# motor_controller_logic.net
KiCad netlist of a schematic drawn in EAGLE
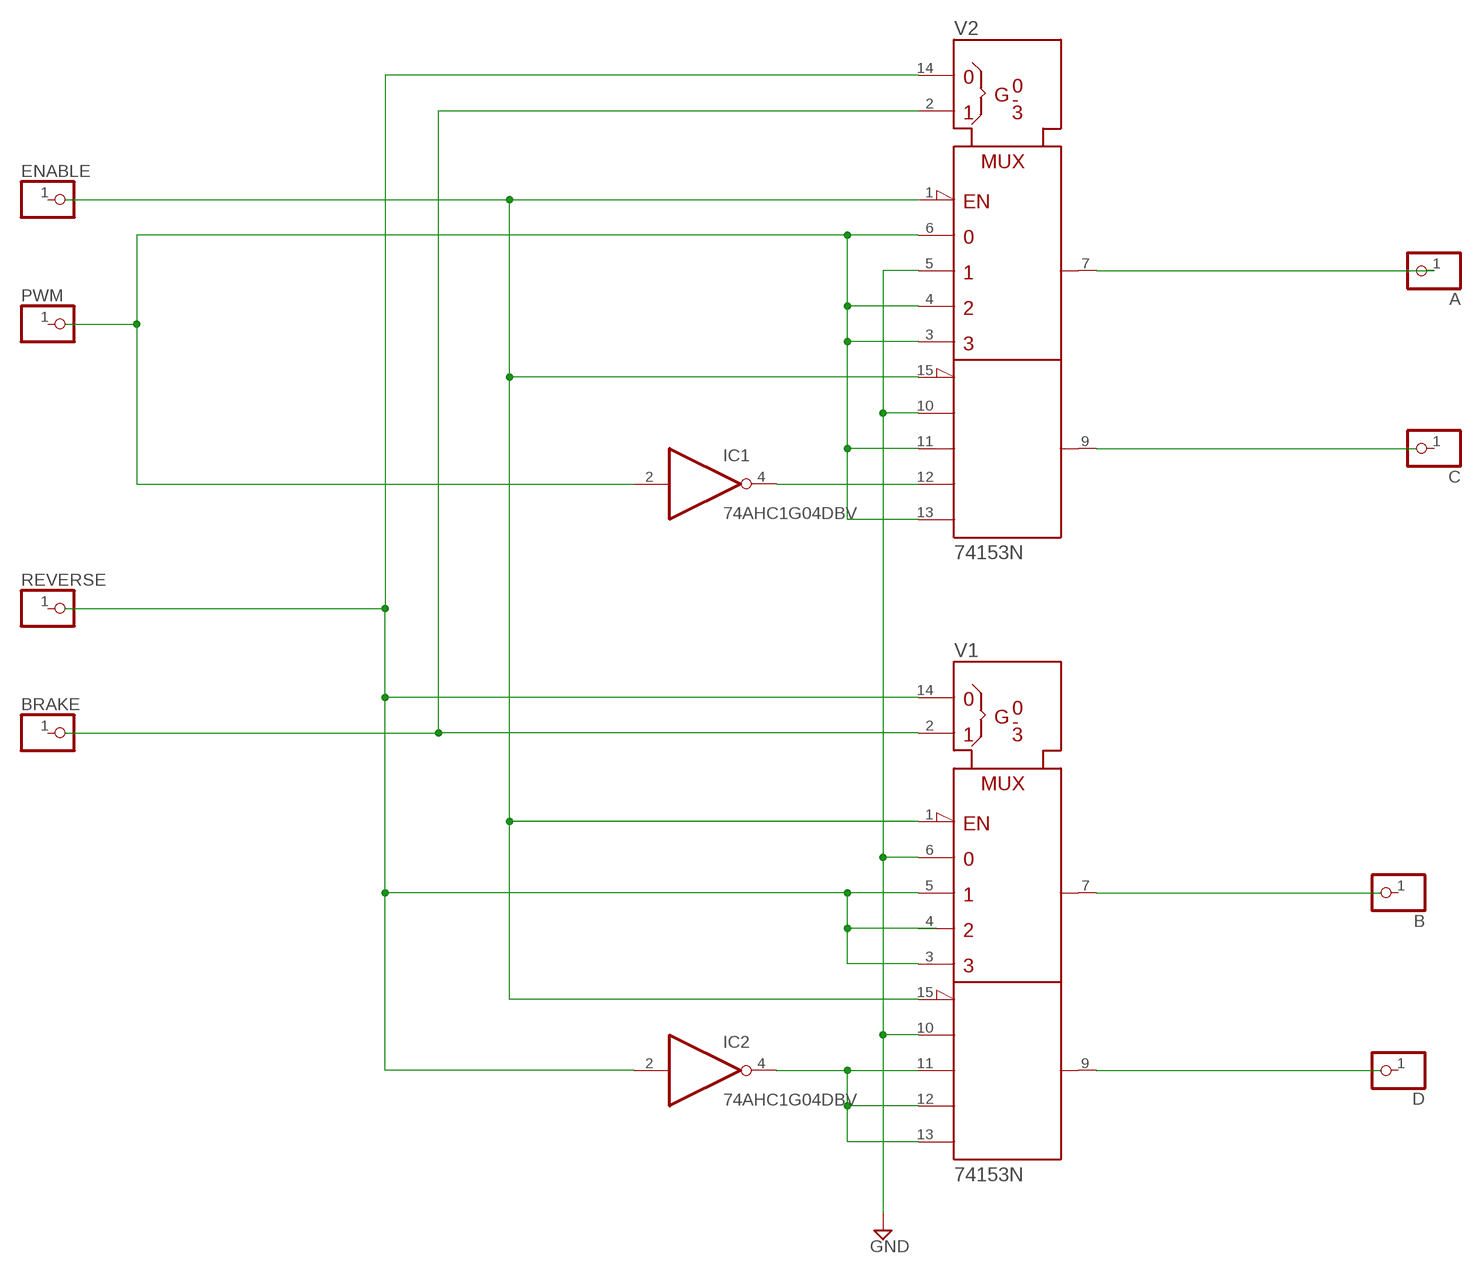
[diagram p0: schematic, sheet 1]

(export (version "E")
  (design (tool "Eeschema 10.0.6"))
  (components
    (comp (ref "A")
      (value "PINHD-1X1")
      (footprint "eagle-import:1X01")
      (libsource (lib "eagle-import") (part "PINHD-1X1"))
    )
    (comp (ref "B")
      (value "PINHD-1X1")
      (footprint "eagle-import:1X01")
      (libsource (lib "eagle-import") (part "PINHD-1X1"))
    )
    (comp (ref "BRAKE")
      (value "PINHD-1X1")
      (footprint "eagle-import:1X01")
      (libsource (lib "eagle-import") (part "PINHD-1X1"))
    )
    (comp (ref "C")
      (value "PINHD-1X1")
      (footprint "eagle-import:1X01")
      (libsource (lib "eagle-import") (part "PINHD-1X1"))
    )
    (comp (ref "D")
      (value "PINHD-1X1")
      (footprint "eagle-import:1X01")
      (libsource (lib "eagle-import") (part "PINHD-1X1"))
    )
    (comp (ref "ENABLE")
      (value "PINHD-1X1")
      (footprint "eagle-import:1X01")
      (libsource (lib "eagle-import") (part "PINHD-1X1"))
    )
    (comp (ref "IC1")
      (value "74AHC1G04DBV")
      (footprint "eagle-import:SOT23-5")
      (libsource (lib "eagle-import") (part "741G04DBVAHC"))
    )
    (comp (ref "IC2")
      (value "74AHC1G04DBV")
      (footprint "eagle-import:SOT23-5")
      (libsource (lib "eagle-import") (part "741G04DBVAHC"))
    )
    (comp (ref "PWM")
      (value "PINHD-1X1")
      (footprint "eagle-import:1X01")
      (libsource (lib "eagle-import") (part "PINHD-1X1"))
    )
    (comp (ref "REVERSE")
      (value "PINHD-1X1")
      (footprint "eagle-import:1X01")
      (libsource (lib "eagle-import") (part "PINHD-1X1"))
    )
    (comp (ref "V1")
      (value "74153N")
      (footprint "eagle-import:DIL16")
      (libsource (lib "eagle-import") (part "74153N"))
    )
    (comp (ref "V2")
      (value "74153N")
      (footprint "eagle-import:DIL16")
      (libsource (lib "eagle-import") (part "74153N"))
    )
  )
  (nets
    (net (code "1") (name "GND") (class "Default")
      (node (ref "V1") (pin "10") (pinfunction "2C0_10") (pintype "input"))
      (node (ref "V1") (pin "6") (pinfunction "1C0_6") (pintype "input"))
      (node (ref "V2") (pin "10") (pinfunction "2C0_10") (pintype "input"))
      (node (ref "V2") (pin "5") (pinfunction "1C1_5") (pintype "input"))
    )
    (net (code "2") (name "Net-(IC1A-I)") (class "Default")
      (node (ref "IC1") (pin "2") (pinfunction "I_2") (pintype "input"))
      (node (ref "V2") (pin "11") (pinfunction "2C1_11") (pintype "input"))
      (node (ref "V2") (pin "13") (pinfunction "2C3_13") (pintype "input"))
      (node (ref "V2") (pin "3") (pinfunction "1C3_3") (pintype "input"))
      (node (ref "V2") (pin "4") (pinfunction "1C2_4") (pintype "input"))
      (node (ref "V2") (pin "6") (pinfunction "1C0_6") (pintype "input"))
    )
    (net (code "3") (name "Net-(IC1A-O)") (class "Default")
      (node (ref "IC1") (pin "4") (pinfunction "O_4") (pintype "output"))
      (node (ref "V2") (pin "12") (pinfunction "2C2_12") (pintype "input"))
    )
    (net (code "4") (name "Net-(IC2A-I)") (class "Default")
      (node (ref "IC2") (pin "2") (pinfunction "I_2") (pintype "input"))
      (node (ref "V1") (pin "14") (pinfunction "A_14") (pintype "input"))
      (node (ref "V1") (pin "3") (pinfunction "1C3_3") (pintype "input"))
      (node (ref "V1") (pin "5") (pinfunction "1C1_5") (pintype "input"))
      (node (ref "V2") (pin "14") (pinfunction "A_14") (pintype "input"))
    )
    (net (code "5") (name "Net-(IC2A-O)") (class "Default")
      (node (ref "IC2") (pin "4") (pinfunction "O_4") (pintype "output"))
      (node (ref "V1") (pin "11") (pinfunction "2C1_11") (pintype "input"))
      (node (ref "V1") (pin "12") (pinfunction "2C2_12") (pintype "input"))
      (node (ref "V1") (pin "13") (pinfunction "2C3_13") (pintype "input"))
    )
    (net (code "6") (name "Net-(V1C-B)") (class "Default")
      (node (ref "V1") (pin "2") (pinfunction "B_2") (pintype "input"))
      (node (ref "V2") (pin "2") (pinfunction "B_2") (pintype "input"))
    )
    (net (code "7") (name "Net-(V1C-~{1G})") (class "Default")
      (node (ref "V1") (pin "1") (pinfunction "~{1G}_1") (pintype "input"))
      (node (ref "V1") (pin "15") (pinfunction "~{2G}_15") (pintype "input"))
      (node (ref "V2") (pin "1") (pinfunction "~{1G}_1") (pintype "input"))
      (node (ref "V2") (pin "15") (pinfunction "~{2G}_15") (pintype "input"))
    )
    (net (code "8") (name "Net-(V2C-1Y)") (class "Default")
      (node (ref "A") (pin "1") (pinfunction "1_1") (pintype "passive"))
      (node (ref "V2") (pin "7") (pinfunction "1Y_7") (pintype "output"))
    )
    (net (code "9") (name "unconnected-(B-Pad1)") (class "Default")
      (node (ref "B") (pin "1") (pinfunction "1_1") (pintype "passive"))
    )
    (net (code "10") (name "unconnected-(BRAKE-Pad1)") (class "Default")
      (node (ref "BRAKE") (pin "1") (pinfunction "1_1") (pintype "passive"))
    )
    (net (code "11") (name "unconnected-(C-Pad1)") (class "Default")
      (node (ref "C") (pin "1") (pinfunction "1_1") (pintype "passive"))
    )
    (net (code "12") (name "unconnected-(D-Pad1)") (class "Default")
      (node (ref "D") (pin "1") (pinfunction "1_1") (pintype "passive"))
    )
    (net (code "13") (name "unconnected-(ENABLE-Pad1)") (class "Default")
      (node (ref "ENABLE") (pin "1") (pinfunction "1_1") (pintype "passive"))
    )
    (net (code "14") (name "unconnected-(PWM-Pad1)") (class "Default")
      (node (ref "PWM") (pin "1") (pinfunction "1_1") (pintype "passive"))
    )
    (net (code "15") (name "unconnected-(REVERSE-Pad1)") (class "Default")
      (node (ref "REVERSE") (pin "1") (pinfunction "1_1") (pintype "passive"))
    )
    (net (code "16") (name "unconnected-(V1C-1C2-Pad4)") (class "Default")
      (node (ref "V1") (pin "4") (pinfunction "1C2_4") (pintype "input"))
    )
    (net (code "17") (name "unconnected-(V1C-1Y-Pad7)") (class "Default")
      (node (ref "V1") (pin "7") (pinfunction "1Y_7") (pintype "output"))
    )
    (net (code "18") (name "unconnected-(V1C-2Y-Pad9)") (class "Default")
      (node (ref "V1") (pin "9") (pinfunction "2Y_9") (pintype "output"))
    )
    (net (code "19") (name "unconnected-(V2C-2Y-Pad9)") (class "Default")
      (node (ref "V2") (pin "9") (pinfunction "2Y_9") (pintype "output"))
    )
  )
)
